# Cellphone.net
KiCad netlist of a schematic drawn in EAGLE
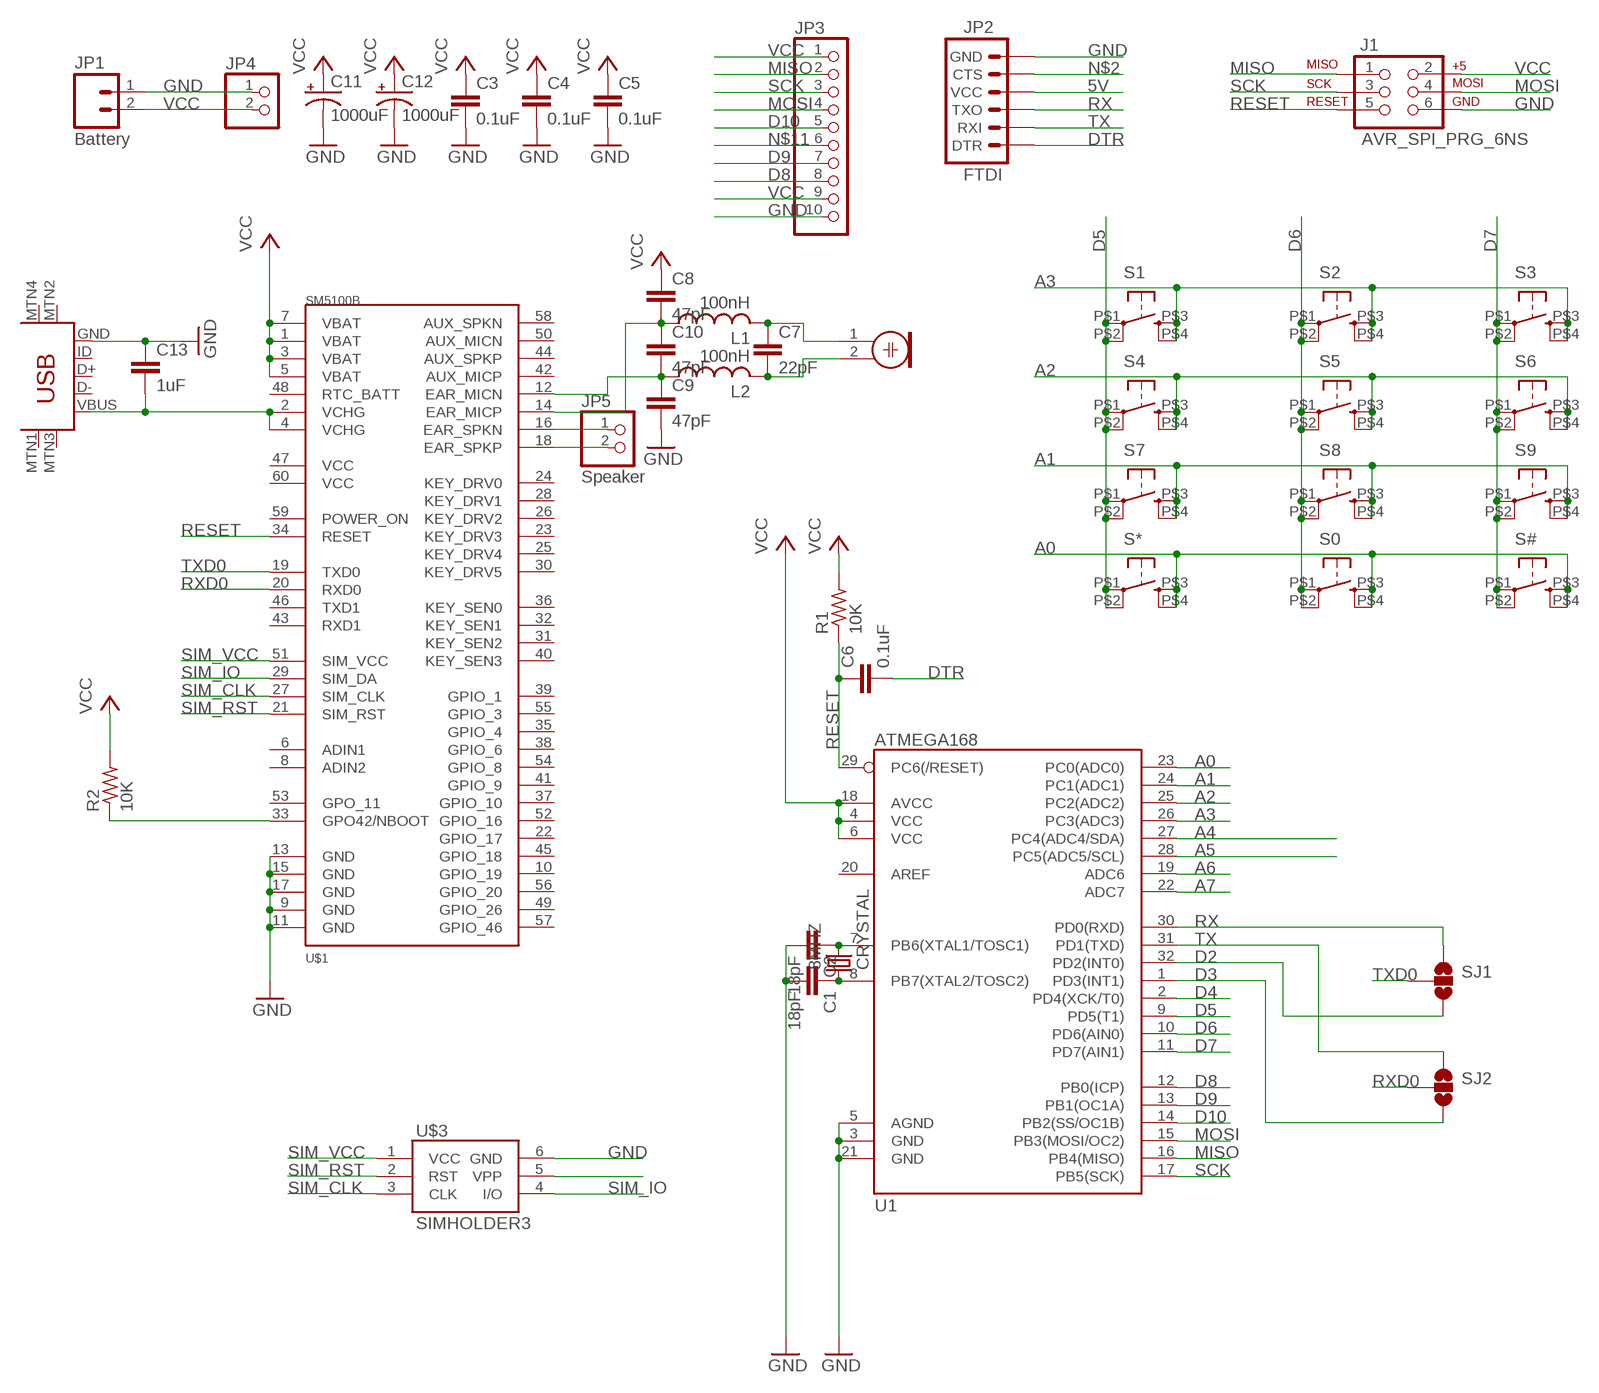
[diagram p0: schematic, sheet 1]

(export (version "E")
  (design (tool "Eeschema 10.0.6"))
  (components
    (comp (ref "8MHZ")
      (value "CRYSTAL")
      (footprint "eagle-import:2-SMD-5X3MM")
      (libsource (lib "eagle-import") (part "CRYSTAL"))
    )
    (comp (ref "C1")
      (value "18pF")
      (footprint "eagle-import:C1206")
      (libsource (lib "eagle-import") (part "C-EUC1206"))
    )
    (comp (ref "C2")
      (value "18pF")
      (footprint "eagle-import:C1206")
      (libsource (lib "eagle-import") (part "C-EUC1206"))
    )
    (comp (ref "C3")
      (value "0.1uF")
      (footprint "eagle-import:C1206")
      (libsource (lib "eagle-import") (part "C-EUC1206"))
    )
    (comp (ref "C4")
      (value "0.1uF")
      (footprint "eagle-import:C1206")
      (libsource (lib "eagle-import") (part "C-EUC1206"))
    )
    (comp (ref "C5")
      (value "0.1uF")
      (footprint "eagle-import:C1206")
      (libsource (lib "eagle-import") (part "C-EUC1206"))
    )
    (comp (ref "C6")
      (value "0.1uF")
      (footprint "eagle-import:C1206")
      (libsource (lib "eagle-import") (part "C-EUC1206"))
    )
    (comp (ref "C7")
      (value "22pF")
      (footprint "eagle-import:C1206")
      (libsource (lib "eagle-import") (part "C-EUC1206"))
    )
    (comp (ref "C8")
      (value "47pF")
      (footprint "eagle-import:C1206")
      (libsource (lib "eagle-import") (part "C-EUC1206"))
    )
    (comp (ref "C9")
      (value "47pF")
      (footprint "eagle-import:C1206")
      (libsource (lib "eagle-import") (part "C-EUC1206"))
    )
    (comp (ref "C10")
      (value "47pF")
      (footprint "eagle-import:C1206")
      (libsource (lib "eagle-import") (part "C-EUC1206"))
    )
    (comp (ref "C11")
      (value "1000uF")
      (footprint "eagle-import:D_7343-31R")
      (libsource (lib "eagle-import") (part "CPOL-USD/7343-31R"))
    )
    (comp (ref "C12")
      (value "1000uF")
      (footprint "eagle-import:D_7343-31R")
      (libsource (lib "eagle-import") (part "CPOL-USD/7343-31R"))
    )
    (comp (ref "C13")
      (value "1uF")
      (footprint "eagle-import:C1206")
      (libsource (lib "eagle-import") (part "C-EUC1206"))
    )
    (comp (ref "J1")
      (value "AVR_SPI_PRG_6NS")
      (footprint "eagle-import:2X3-NS")
      (libsource (lib "eagle-import") (part "AVR_SPI_PRG_6NS"))
    )
    (comp (ref "JP1")
      (value "Battery")
      (footprint "eagle-import:JST-2-SMD")
      (libsource (lib "eagle-import") (part "M02-JST-2MM-SMT"))
    )
    (comp (ref "JP2")
      (value "FTDI")
      (footprint "eagle-import:1X06")
      (libsource (lib "eagle-import") (part "ARDUINO_SERIAL_PROGRAMPTH"))
    )
    (comp (ref "JP3")
      (value "TFT160X128")
      (footprint "eagle-import:TFT1.8")
      (libsource (lib "eagle-import") (part "TFT160X128"))
    )
    (comp (ref "JP4")
      (value "PINHD-1X2")
      (footprint "eagle-import:1X02")
      (libsource (lib "eagle-import") (part "PINHD-1X2"))
    )
    (comp (ref "JP5")
      (value "Speaker")
      (footprint "eagle-import:1X02")
      (libsource (lib "eagle-import") (part "PINHD-1X2"))
    )
    (comp (ref "L1")
      (value "100nH")
      (footprint "eagle-import:L2012C")
      (libsource (lib "eagle-import") (part "L-USL2012C"))
    )
    (comp (ref "L2")
      (value "100nH")
      (footprint "eagle-import:L2012C")
      (libsource (lib "eagle-import") (part "L-USL2012C"))
    )
    (comp (ref "M1")
      (value "ELECTRET_MICROPHON-WM-64PC/64PK")
      (footprint "eagle-import:WM-64PC_64PK")
      (libsource (lib "eagle-import") (part "ELECTRET_MICROPHON-WM-64PC/64PK"))
    )
    (comp (ref "R1")
      (value "10K")
      (footprint "eagle-import:R1206")
      (libsource (lib "eagle-import") (part "R-US_R1206"))
    )
    (comp (ref "R2")
      (value "10K")
      (footprint "eagle-import:R1206")
      (libsource (lib "eagle-import") (part "R-US_R1206"))
    )
    (comp (ref "S#")
      (value "SWITCH-JLEAD")
      (footprint "eagle-import:BUTTON_6MM_JLEAD")
      (libsource (lib "eagle-import") (part "SWITCH-JLEAD"))
    )
    (comp (ref "S*")
      (value "SWITCH-JLEAD")
      (footprint "eagle-import:BUTTON_6MM_JLEAD")
      (libsource (lib "eagle-import") (part "SWITCH-JLEAD"))
    )
    (comp (ref "S0")
      (value "SWITCH-JLEAD")
      (footprint "eagle-import:BUTTON_6MM_JLEAD")
      (libsource (lib "eagle-import") (part "SWITCH-JLEAD"))
    )
    (comp (ref "S1")
      (value "SWITCH-JLEAD")
      (footprint "eagle-import:BUTTON_6MM_JLEAD")
      (libsource (lib "eagle-import") (part "SWITCH-JLEAD"))
    )
    (comp (ref "S2")
      (value "SWITCH-JLEAD")
      (footprint "eagle-import:BUTTON_6MM_JLEAD")
      (libsource (lib "eagle-import") (part "SWITCH-JLEAD"))
    )
    (comp (ref "S3")
      (value "SWITCH-JLEAD")
      (footprint "eagle-import:BUTTON_6MM_JLEAD")
      (libsource (lib "eagle-import") (part "SWITCH-JLEAD"))
    )
    (comp (ref "S4")
      (value "SWITCH-JLEAD")
      (footprint "eagle-import:BUTTON_6MM_JLEAD")
      (libsource (lib "eagle-import") (part "SWITCH-JLEAD"))
    )
    (comp (ref "S5")
      (value "SWITCH-JLEAD")
      (footprint "eagle-import:BUTTON_6MM_JLEAD")
      (libsource (lib "eagle-import") (part "SWITCH-JLEAD"))
    )
    (comp (ref "S6")
      (value "SWITCH-JLEAD")
      (footprint "eagle-import:BUTTON_6MM_JLEAD")
      (libsource (lib "eagle-import") (part "SWITCH-JLEAD"))
    )
    (comp (ref "S7")
      (value "SWITCH-JLEAD")
      (footprint "eagle-import:BUTTON_6MM_JLEAD")
      (libsource (lib "eagle-import") (part "SWITCH-JLEAD"))
    )
    (comp (ref "S8")
      (value "SWITCH-JLEAD")
      (footprint "eagle-import:BUTTON_6MM_JLEAD")
      (libsource (lib "eagle-import") (part "SWITCH-JLEAD"))
    )
    (comp (ref "S9")
      (value "SWITCH-JLEAD")
      (footprint "eagle-import:BUTTON_6MM_JLEAD")
      (libsource (lib "eagle-import") (part "SWITCH-JLEAD"))
    )
    (comp (ref "SJ1")
      (value "SOLDERJUMPER_2WAYPASTE1&2")
      (footprint "eagle-import:SJ_3_PASTE1&2")
      (libsource (lib "eagle-import") (part "SOLDERJUMPER_2WAYPASTE1&2"))
    )
    (comp (ref "SJ2")
      (value "SOLDERJUMPER_2WAYPASTE1&2")
      (footprint "eagle-import:SJ_3_PASTE1&2")
      (libsource (lib "eagle-import") (part "SOLDERJUMPER_2WAYPASTE1&2"))
    )
    (comp (ref "U$1")
      (value "SM5100B")
      (footprint "eagle-import:SM5100B")
      (libsource (lib "eagle-import") (part "SM5100B"))
    )
    (comp (ref "U$2")
      (value "USB-MINIB-5PIN")
      (footprint "eagle-import:USB-MINIB")
      (libsource (lib "eagle-import") (part "USB-MINIB-5PIN"))
    )
    (comp (ref "U$3")
      (value "SIMHOLDER3")
      (footprint "eagle-import:SIMHOLDER3")
      (libsource (lib "eagle-import") (part "SIMHOLDER3"))
    )
    (comp (ref "U1")
      (value "ATMEGA168")
      (footprint "eagle-import:TQFP32-08")
      (libsource (lib "eagle-import") (part "ATMEGA168"))
    )
  )
  (nets
    (net (code "1") (name "/5V") (class "Default")
      (node (ref "JP2") (pin "4") (pinfunction "VCC_4") (pintype "passive"))
    )
    (net (code "2") (name "/A0") (class "Default")
      (node (ref "S#") (pin "P$3") (pinfunction "S_P$3") (pintype "passive"))
      (node (ref "S#") (pin "P$4") (pinfunction "S1_P$4") (pintype "passive"))
      (node (ref "S*") (pin "P$3") (pinfunction "S_P$3") (pintype "passive"))
      (node (ref "S*") (pin "P$4") (pinfunction "S1_P$4") (pintype "passive"))
      (node (ref "S0") (pin "P$3") (pinfunction "S_P$3") (pintype "passive"))
      (node (ref "S0") (pin "P$4") (pinfunction "S1_P$4") (pintype "passive"))
      (node (ref "U1") (pin "23") (pinfunction "PC0(ADC0)_23") (pintype "bidirectional"))
    )
    (net (code "3") (name "/A1") (class "Default")
      (node (ref "S7") (pin "P$3") (pinfunction "S_P$3") (pintype "passive"))
      (node (ref "S7") (pin "P$4") (pinfunction "S1_P$4") (pintype "passive"))
      (node (ref "S8") (pin "P$3") (pinfunction "S_P$3") (pintype "passive"))
      (node (ref "S8") (pin "P$4") (pinfunction "S1_P$4") (pintype "passive"))
      (node (ref "S9") (pin "P$3") (pinfunction "S_P$3") (pintype "passive"))
      (node (ref "S9") (pin "P$4") (pinfunction "S1_P$4") (pintype "passive"))
      (node (ref "U1") (pin "24") (pinfunction "PC1(ADC1)_24") (pintype "bidirectional"))
    )
    (net (code "4") (name "/A2") (class "Default")
      (node (ref "S4") (pin "P$3") (pinfunction "S_P$3") (pintype "passive"))
      (node (ref "S4") (pin "P$4") (pinfunction "S1_P$4") (pintype "passive"))
      (node (ref "S5") (pin "P$3") (pinfunction "S_P$3") (pintype "passive"))
      (node (ref "S5") (pin "P$4") (pinfunction "S1_P$4") (pintype "passive"))
      (node (ref "S6") (pin "P$3") (pinfunction "S_P$3") (pintype "passive"))
      (node (ref "S6") (pin "P$4") (pinfunction "S1_P$4") (pintype "passive"))
      (node (ref "U1") (pin "25") (pinfunction "PC2(ADC2)_25") (pintype "bidirectional"))
    )
    (net (code "5") (name "/A3") (class "Default")
      (node (ref "S1") (pin "P$3") (pinfunction "S_P$3") (pintype "passive"))
      (node (ref "S1") (pin "P$4") (pinfunction "S1_P$4") (pintype "passive"))
      (node (ref "S2") (pin "P$3") (pinfunction "S_P$3") (pintype "passive"))
      (node (ref "S2") (pin "P$4") (pinfunction "S1_P$4") (pintype "passive"))
      (node (ref "S3") (pin "P$3") (pinfunction "S_P$3") (pintype "passive"))
      (node (ref "S3") (pin "P$4") (pinfunction "S1_P$4") (pintype "passive"))
      (node (ref "U1") (pin "26") (pinfunction "PC3(ADC3)_26") (pintype "bidirectional"))
    )
    (net (code "6") (name "/A4") (class "Default")
      (node (ref "U1") (pin "27") (pinfunction "PC4(ADC4/SDA)_27") (pintype "bidirectional"))
    )
    (net (code "7") (name "/A5") (class "Default")
      (node (ref "U1") (pin "28") (pinfunction "PC5(ADC5/SCL)_28") (pintype "bidirectional"))
    )
    (net (code "8") (name "/A6") (class "Default")
      (node (ref "U1") (pin "19") (pinfunction "ADC6_19") (pintype "bidirectional"))
    )
    (net (code "9") (name "/A7") (class "Default")
      (node (ref "U1") (pin "22") (pinfunction "ADC7_22") (pintype "bidirectional"))
    )
    (net (code "10") (name "/D2") (class "Default")
      (node (ref "SJ1") (pin "3") (pinfunction "3_3") (pintype "passive"))
      (node (ref "U1") (pin "32") (pinfunction "PD2(INT0)_32") (pintype "bidirectional"))
    )
    (net (code "11") (name "/D3") (class "Default")
      (node (ref "SJ2") (pin "3") (pinfunction "3_3") (pintype "passive"))
      (node (ref "U1") (pin "1") (pinfunction "PD3(INT1)_1") (pintype "bidirectional"))
    )
    (net (code "12") (name "/D4") (class "Default")
      (node (ref "U1") (pin "2") (pinfunction "PD4(XCK/T0)_2") (pintype "bidirectional"))
    )
    (net (code "13") (name "/D5") (class "Default")
      (node (ref "S*") (pin "P$1") (pinfunction "P_P$1") (pintype "passive"))
      (node (ref "S*") (pin "P$2") (pinfunction "P1_P$2") (pintype "passive"))
      (node (ref "S1") (pin "P$1") (pinfunction "P_P$1") (pintype "passive"))
      (node (ref "S1") (pin "P$2") (pinfunction "P1_P$2") (pintype "passive"))
      (node (ref "S4") (pin "P$1") (pinfunction "P_P$1") (pintype "passive"))
      (node (ref "S4") (pin "P$2") (pinfunction "P1_P$2") (pintype "passive"))
      (node (ref "S7") (pin "P$1") (pinfunction "P_P$1") (pintype "passive"))
      (node (ref "S7") (pin "P$2") (pinfunction "P1_P$2") (pintype "passive"))
      (node (ref "U1") (pin "9") (pinfunction "PD5(T1)_9") (pintype "bidirectional"))
    )
    (net (code "14") (name "/D6") (class "Default")
      (node (ref "S0") (pin "P$1") (pinfunction "P_P$1") (pintype "passive"))
      (node (ref "S0") (pin "P$2") (pinfunction "P1_P$2") (pintype "passive"))
      (node (ref "S2") (pin "P$1") (pinfunction "P_P$1") (pintype "passive"))
      (node (ref "S2") (pin "P$2") (pinfunction "P1_P$2") (pintype "passive"))
      (node (ref "S5") (pin "P$1") (pinfunction "P_P$1") (pintype "passive"))
      (node (ref "S5") (pin "P$2") (pinfunction "P1_P$2") (pintype "passive"))
      (node (ref "S8") (pin "P$1") (pinfunction "P_P$1") (pintype "passive"))
      (node (ref "S8") (pin "P$2") (pinfunction "P1_P$2") (pintype "passive"))
      (node (ref "U1") (pin "10") (pinfunction "PD6(AIN0)_10") (pintype "bidirectional"))
    )
    (net (code "15") (name "/D7") (class "Default")
      (node (ref "S#") (pin "P$1") (pinfunction "P_P$1") (pintype "passive"))
      (node (ref "S#") (pin "P$2") (pinfunction "P1_P$2") (pintype "passive"))
      (node (ref "S3") (pin "P$1") (pinfunction "P_P$1") (pintype "passive"))
      (node (ref "S3") (pin "P$2") (pinfunction "P1_P$2") (pintype "passive"))
      (node (ref "S6") (pin "P$1") (pinfunction "P_P$1") (pintype "passive"))
      (node (ref "S6") (pin "P$2") (pinfunction "P1_P$2") (pintype "passive"))
      (node (ref "S9") (pin "P$1") (pinfunction "P_P$1") (pintype "passive"))
      (node (ref "S9") (pin "P$2") (pinfunction "P1_P$2") (pintype "passive"))
      (node (ref "U1") (pin "11") (pinfunction "PD7(AIN1)_11") (pintype "bidirectional"))
    )
    (net (code "16") (name "/D8") (class "Default")
      (node (ref "JP3") (pin "8") (pinfunction "RESET_8") (pintype "passive"))
      (node (ref "U1") (pin "12") (pinfunction "PB0(ICP)_12") (pintype "bidirectional"))
    )
    (net (code "17") (name "/D9") (class "Default")
      (node (ref "JP3") (pin "7") (pinfunction "D/C_7") (pintype "passive"))
      (node (ref "U1") (pin "13") (pinfunction "PB1(OC1A)_13") (pintype "bidirectional"))
    )
    (net (code "18") (name "/D10") (class "Default")
      (node (ref "JP3") (pin "5") (pinfunction "TFT_CS_5") (pintype "passive"))
      (node (ref "U1") (pin "14") (pinfunction "PB2(SS/OC1B)_14") (pintype "bidirectional"))
    )
    (net (code "19") (name "/DTR") (class "Default")
      (node (ref "C6") (pin "2") (pinfunction "2_2") (pintype "passive"))
      (node (ref "JP2") (pin "1") (pinfunction "DTR_1") (pintype "passive"))
    )
    (net (code "20") (name "/MISO") (class "Default")
      (node (ref "J1") (pin "1") (pinfunction "1_1") (pintype "passive"))
      (node (ref "JP3") (pin "2") (pinfunction "MISO_2") (pintype "passive"))
      (node (ref "U1") (pin "16") (pinfunction "PB4(MISO)_16") (pintype "bidirectional"))
    )
    (net (code "21") (name "/MOSI") (class "Default")
      (node (ref "J1") (pin "4") (pinfunction "4_4") (pintype "passive"))
      (node (ref "JP3") (pin "4") (pinfunction "MOSI_4") (pintype "passive"))
      (node (ref "U1") (pin "15") (pinfunction "PB3(MOSI/OC2)_15") (pintype "bidirectional"))
    )
    (net (code "22") (name "/N$2") (class "Default")
      (node (ref "JP2") (pin "5") (pinfunction "CTS_5") (pintype "passive"))
    )
    (net (code "23") (name "/N$11") (class "Default")
      (node (ref "JP3") (pin "6") (pinfunction "CARD_CS_6") (pintype "passive"))
    )
    (net (code "24") (name "/RESET") (class "Default")
      (node (ref "C6") (pin "1") (pinfunction "1_1") (pintype "passive"))
      (node (ref "J1") (pin "5") (pinfunction "5_5") (pintype "passive"))
      (node (ref "R1") (pin "1") (pinfunction "1_1") (pintype "passive"))
      (node (ref "U$1") (pin "34") (pinfunction "RESET_34") (pintype "bidirectional"))
      (node (ref "U1") (pin "29") (pinfunction "PC6(/RESET)_29") (pintype "bidirectional"))
    )
    (net (code "25") (name "/RX") (class "Default")
      (node (ref "JP2") (pin "3") (pinfunction "TXO_3") (pintype "passive"))
      (node (ref "SJ1") (pin "1") (pinfunction "1_1") (pintype "passive"))
      (node (ref "U1") (pin "30") (pinfunction "PD0(RXD)_30") (pintype "bidirectional"))
    )
    (net (code "26") (name "/RXD0") (class "Default")
      (node (ref "SJ2") (pin "2") (pinfunction "2_2") (pintype "passive"))
      (node (ref "U$1") (pin "20") (pinfunction "RXD0_20") (pintype "bidirectional"))
    )
    (net (code "27") (name "/SCK") (class "Default")
      (node (ref "J1") (pin "3") (pinfunction "3_3") (pintype "passive"))
      (node (ref "JP3") (pin "3") (pinfunction "SCK_3") (pintype "passive"))
      (node (ref "U1") (pin "17") (pinfunction "PB5(SCK)_17") (pintype "bidirectional"))
    )
    (net (code "28") (name "/SIM_CLK") (class "Default")
      (node (ref "U$1") (pin "27") (pinfunction "SIM_CLK_27") (pintype "bidirectional"))
      (node (ref "U$3") (pin "3") (pinfunction "CLK_3") (pintype "bidirectional"))
    )
    (net (code "29") (name "/SIM_IO") (class "Default")
      (node (ref "U$1") (pin "29") (pinfunction "SIM_DA_29") (pintype "bidirectional"))
      (node (ref "U$3") (pin "4") (pinfunction "I/O_4") (pintype "bidirectional"))
    )
    (net (code "30") (name "/SIM_RST") (class "Default")
      (node (ref "U$1") (pin "21") (pinfunction "SIM_RST_21") (pintype "bidirectional"))
      (node (ref "U$3") (pin "2") (pinfunction "RST_2") (pintype "bidirectional"))
    )
    (net (code "31") (name "/SIM_VCC") (class "Default")
      (node (ref "U$1") (pin "51") (pinfunction "SIM_VCC_51") (pintype "bidirectional"))
      (node (ref "U$3") (pin "1") (pinfunction "VCC_1") (pintype "bidirectional"))
    )
    (net (code "32") (name "/TX") (class "Default")
      (node (ref "JP2") (pin "2") (pinfunction "RXI_2") (pintype "passive"))
      (node (ref "SJ2") (pin "1") (pinfunction "1_1") (pintype "passive"))
      (node (ref "U1") (pin "31") (pinfunction "PD1(TXD)_31") (pintype "bidirectional"))
    )
    (net (code "33") (name "/TXD0") (class "Default")
      (node (ref "SJ1") (pin "2") (pinfunction "2_2") (pintype "passive"))
      (node (ref "U$1") (pin "19") (pinfunction "TXD0_19") (pintype "bidirectional"))
    )
    (net (code "34") (name "GND") (class "Default")
      (node (ref "C1") (pin "2") (pinfunction "2_2") (pintype "passive"))
      (node (ref "C11") (pin "-") (pinfunction "-_-") (pintype "passive"))
      (node (ref "C12") (pin "-") (pinfunction "-_-") (pintype "passive"))
      (node (ref "C13") (pin "1") (pinfunction "1_1") (pintype "passive"))
      (node (ref "C2") (pin "2") (pinfunction "2_2") (pintype "passive"))
      (node (ref "C3") (pin "2") (pinfunction "2_2") (pintype "passive"))
      (node (ref "C4") (pin "2") (pinfunction "2_2") (pintype "passive"))
      (node (ref "C5") (pin "2") (pinfunction "2_2") (pintype "passive"))
      (node (ref "C9") (pin "2") (pinfunction "2_2") (pintype "passive"))
      (node (ref "J1") (pin "6") (pinfunction "6_6") (pintype "passive"))
      (node (ref "JP1") (pin "1") (pinfunction "2_1") (pintype "passive"))
      (node (ref "JP2") (pin "6") (pinfunction "GND_6") (pintype "passive"))
      (node (ref "JP3") (pin "10") (pinfunction "GND_10") (pintype "passive"))
      (node (ref "JP4") (pin "1") (pinfunction "1_1") (pintype "passive"))
      (node (ref "U$1") (pin "11") (pinfunction "GND_11") (pintype "bidirectional"))
      (node (ref "U$1") (pin "13") (pinfunction "GND_13") (pintype "bidirectional"))
      (node (ref "U$1") (pin "15") (pinfunction "GND_15") (pintype "bidirectional"))
      (node (ref "U$1") (pin "17") (pinfunction "GND_17") (pintype "bidirectional"))
      (node (ref "U$1") (pin "9") (pinfunction "GND_9") (pintype "bidirectional"))
      (node (ref "U$2") (pin "GND") (pinfunction "GND_GND") (pintype "bidirectional"))
      (node (ref "U$3") (pin "6") (pinfunction "GND_6") (pintype "bidirectional"))
      (node (ref "U1") (pin "21") (pinfunction "GND_21") (pintype "bidirectional"))
      (node (ref "U1") (pin "3") (pinfunction "GND_3") (pintype "bidirectional"))
      (node (ref "U1") (pin "5") (pinfunction "AGND_5") (pintype "bidirectional"))
    )
    (net (code "35") (name "Net-(8MHZ-1)") (class "Default")
      (node (ref "8MHZ") (pin "P$1") (pinfunction "1_P$1") (pintype "passive"))
      (node (ref "C1") (pin "1") (pinfunction "1_1") (pintype "passive"))
      (node (ref "U1") (pin "8") (pinfunction "PB7(XTAL2/TOSC2)_8") (pintype "bidirectional"))
    )
    (net (code "36") (name "Net-(8MHZ-2)") (class "Default")
      (node (ref "8MHZ") (pin "P$2") (pinfunction "2_P$2") (pintype "passive"))
      (node (ref "C2") (pin "1") (pinfunction "1_1") (pintype "passive"))
      (node (ref "U1") (pin "7") (pinfunction "PB6(XTAL1/TOSC1)_7") (pintype "bidirectional"))
    )
    (net (code "37") (name "Net-(C7-Pad1)") (class "Default")
      (node (ref "C7") (pin "1") (pinfunction "1_1") (pintype "passive"))
      (node (ref "L1") (pin "2") (pinfunction "2_2") (pintype "passive"))
      (node (ref "M1") (pin "1") (pinfunction "1_1") (pintype "passive"))
    )
    (net (code "38") (name "Net-(C7-Pad2)") (class "Default")
      (node (ref "C7") (pin "2") (pinfunction "2_2") (pintype "passive"))
      (node (ref "L2") (pin "2") (pinfunction "2_2") (pintype "passive"))
      (node (ref "M1") (pin "2") (pinfunction "2_2") (pintype "passive"))
    )
    (net (code "39") (name "Net-(C13-Pad2)") (class "Default")
      (node (ref "C13") (pin "2") (pinfunction "2_2") (pintype "passive"))
      (node (ref "U$1") (pin "2") (pinfunction "VCHG_2") (pintype "bidirectional"))
      (node (ref "U$1") (pin "4") (pinfunction "VCHG_4") (pintype "bidirectional"))
      (node (ref "U$2") (pin "VBUS") (pinfunction "VBUS_VBUS") (pintype "bidirectional"))
    )
    (net (code "40") (name "Net-(U$1-EAR_MICN)") (class "Default")
      (node (ref "C10") (pin "2") (pinfunction "2_2") (pintype "passive"))
      (node (ref "C9") (pin "1") (pinfunction "1_1") (pintype "passive"))
      (node (ref "L2") (pin "1") (pinfunction "1_1") (pintype "passive"))
      (node (ref "U$1") (pin "12") (pinfunction "EAR_MICN_12") (pintype "bidirectional"))
    )
    (net (code "41") (name "Net-(U$1-EAR_MICP)") (class "Default")
      (node (ref "C10") (pin "1") (pinfunction "1_1") (pintype "passive"))
      (node (ref "C8") (pin "2") (pinfunction "2_2") (pintype "passive"))
      (node (ref "L1") (pin "1") (pinfunction "1_1") (pintype "passive"))
      (node (ref "U$1") (pin "14") (pinfunction "EAR_MICP_14") (pintype "bidirectional"))
    )
    (net (code "42") (name "Net-(U$1-EAR_SPKN)") (class "Default")
      (node (ref "JP5") (pin "1") (pinfunction "1_1") (pintype "passive"))
      (node (ref "U$1") (pin "16") (pinfunction "EAR_SPKN_16") (pintype "bidirectional"))
    )
    (net (code "43") (name "Net-(U$1-EAR_SPKP)") (class "Default")
      (node (ref "JP5") (pin "2") (pinfunction "2_2") (pintype "passive"))
      (node (ref "U$1") (pin "18") (pinfunction "EAR_SPKP_18") (pintype "bidirectional"))
    )
    (net (code "44") (name "Net-(U$1-GPO42{slash}NBOOT)") (class "Default")
      (node (ref "R2") (pin "1") (pinfunction "1_1") (pintype "passive"))
      (node (ref "U$1") (pin "33") (pinfunction "GPO42/NBOOT_33") (pintype "bidirectional"))
    )
    (net (code "45") (name "VCC") (class "Default")
      (node (ref "C11") (pin "+") (pinfunction "+_+") (pintype "passive"))
      (node (ref "C12") (pin "+") (pinfunction "+_+") (pintype "passive"))
      (node (ref "C3") (pin "1") (pinfunction "1_1") (pintype "passive"))
      (node (ref "C4") (pin "1") (pinfunction "1_1") (pintype "passive"))
      (node (ref "C5") (pin "1") (pinfunction "1_1") (pintype "passive"))
      (node (ref "C8") (pin "1") (pinfunction "1_1") (pintype "passive"))
      (node (ref "J1") (pin "2") (pinfunction "2_2") (pintype "passive"))
      (node (ref "JP1") (pin "2") (pinfunction "1_2") (pintype "passive"))
      (node (ref "JP3") (pin "1") (pinfunction "LITE_1") (pintype "passive"))
      (node (ref "JP3") (pin "9") (pinfunction "VCC_9") (pintype "passive"))
      (node (ref "JP4") (pin "2") (pinfunction "2_2") (pintype "passive"))
      (node (ref "R1") (pin "2") (pinfunction "2_2") (pintype "passive"))
      (node (ref "R2") (pin "2") (pinfunction "2_2") (pintype "passive"))
      (node (ref "U$1") (pin "1") (pinfunction "VBAT_1") (pintype "bidirectional"))
      (node (ref "U$1") (pin "3") (pinfunction "VBAT_3") (pintype "bidirectional"))
      (node (ref "U$1") (pin "5") (pinfunction "VBAT_5") (pintype "bidirectional"))
      (node (ref "U$1") (pin "7") (pinfunction "VBAT_7") (pintype "bidirectional"))
      (node (ref "U1") (pin "18") (pinfunction "AVCC_18") (pintype "bidirectional"))
      (node (ref "U1") (pin "4") (pinfunction "VCC_4") (pintype "bidirectional"))
      (node (ref "U1") (pin "6") (pinfunction "VCC_6") (pintype "bidirectional"))
    )
    (net (code "46") (name "unconnected-(U$1-ADIN1-Pad6)") (class "Default")
      (node (ref "U$1") (pin "6") (pinfunction "ADIN1_6") (pintype "bidirectional"))
    )
    (net (code "47") (name "unconnected-(U$1-ADIN2-Pad8)") (class "Default")
      (node (ref "U$1") (pin "8") (pinfunction "ADIN2_8") (pintype "bidirectional"))
    )
    (net (code "48") (name "unconnected-(U$1-AUX_MICN-Pad50)") (class "Default")
      (node (ref "U$1") (pin "50") (pinfunction "AUX_MICN_50") (pintype "bidirectional"))
    )
    (net (code "49") (name "unconnected-(U$1-AUX_MICP-Pad42)") (class "Default")
      (node (ref "U$1") (pin "42") (pinfunction "AUX_MICP_42") (pintype "bidirectional"))
    )
    (net (code "50") (name "unconnected-(U$1-AUX_SPKN-Pad58)") (class "Default")
      (node (ref "U$1") (pin "58") (pinfunction "AUX_SPKN_58") (pintype "bidirectional"))
    )
    (net (code "51") (name "unconnected-(U$1-AUX_SPKP-Pad44)") (class "Default")
      (node (ref "U$1") (pin "44") (pinfunction "AUX_SPKP_44") (pintype "bidirectional"))
    )
    (net (code "52") (name "unconnected-(U$1-GPIO_1-Pad39)") (class "Default")
      (node (ref "U$1") (pin "39") (pinfunction "GPIO_1_39") (pintype "bidirectional"))
    )
    (net (code "53") (name "unconnected-(U$1-GPIO_3-Pad55)") (class "Default")
      (node (ref "U$1") (pin "55") (pinfunction "GPIO_3_55") (pintype "bidirectional"))
    )
    (net (code "54") (name "unconnected-(U$1-GPIO_4-Pad35)") (class "Default")
      (node (ref "U$1") (pin "35") (pinfunction "GPIO_4_35") (pintype "bidirectional"))
    )
    (net (code "55") (name "unconnected-(U$1-GPIO_6-Pad38)") (class "Default")
      (node (ref "U$1") (pin "38") (pinfunction "GPIO_6_38") (pintype "bidirectional"))
    )
    (net (code "56") (name "unconnected-(U$1-GPIO_8-Pad54)") (class "Default")
      (node (ref "U$1") (pin "54") (pinfunction "GPIO_8_54") (pintype "bidirectional"))
    )
    (net (code "57") (name "unconnected-(U$1-GPIO_9-Pad41)") (class "Default")
      (node (ref "U$1") (pin "41") (pinfunction "GPIO_9_41") (pintype "bidirectional"))
    )
    (net (code "58") (name "unconnected-(U$1-GPIO_10-Pad37)") (class "Default")
      (node (ref "U$1") (pin "37") (pinfunction "GPIO_10_37") (pintype "bidirectional"))
    )
    (net (code "59") (name "unconnected-(U$1-GPIO_16-Pad52)") (class "Default")
      (node (ref "U$1") (pin "52") (pinfunction "GPIO_16_52") (pintype "bidirectional"))
    )
    (net (code "60") (name "unconnected-(U$1-GPIO_17-Pad22)") (class "Default")
      (node (ref "U$1") (pin "22") (pinfunction "GPIO_17_22") (pintype "bidirectional"))
    )
    (net (code "61") (name "unconnected-(U$1-GPIO_18-Pad45)") (class "Default")
      (node (ref "U$1") (pin "45") (pinfunction "GPIO_18_45") (pintype "bidirectional"))
    )
    (net (code "62") (name "unconnected-(U$1-GPIO_19-Pad10)") (class "Default")
      (node (ref "U$1") (pin "10") (pinfunction "GPIO_19_10") (pintype "bidirectional"))
    )
    (net (code "63") (name "unconnected-(U$1-GPIO_20-Pad56)") (class "Default")
      (node (ref "U$1") (pin "56") (pinfunction "GPIO_20_56") (pintype "bidirectional"))
    )
    (net (code "64") (name "unconnected-(U$1-GPIO_26-Pad49)") (class "Default")
      (node (ref "U$1") (pin "49") (pinfunction "GPIO_26_49") (pintype "bidirectional"))
    )
    (net (code "65") (name "unconnected-(U$1-GPIO_46-Pad57)") (class "Default")
      (node (ref "U$1") (pin "57") (pinfunction "GPIO_46_57") (pintype "bidirectional"))
    )
    (net (code "66") (name "unconnected-(U$1-GPO_11-Pad53)") (class "Default")
      (node (ref "U$1") (pin "53") (pinfunction "GPO_11_53") (pintype "bidirectional"))
    )
    (net (code "67") (name "unconnected-(U$1-KEY_DRV0-Pad24)") (class "Default")
      (node (ref "U$1") (pin "24") (pinfunction "KEY_DRV0_24") (pintype "bidirectional"))
    )
    (net (code "68") (name "unconnected-(U$1-KEY_DRV1-Pad28)") (class "Default")
      (node (ref "U$1") (pin "28") (pinfunction "KEY_DRV1_28") (pintype "bidirectional"))
    )
    (net (code "69") (name "unconnected-(U$1-KEY_DRV2-Pad26)") (class "Default")
      (node (ref "U$1") (pin "26") (pinfunction "KEY_DRV2_26") (pintype "bidirectional"))
    )
    (net (code "70") (name "unconnected-(U$1-KEY_DRV3-Pad23)") (class "Default")
      (node (ref "U$1") (pin "23") (pinfunction "KEY_DRV3_23") (pintype "bidirectional"))
    )
    (net (code "71") (name "unconnected-(U$1-KEY_DRV4-Pad25)") (class "Default")
      (node (ref "U$1") (pin "25") (pinfunction "KEY_DRV4_25") (pintype "bidirectional"))
    )
    (net (code "72") (name "unconnected-(U$1-KEY_DRV5-Pad30)") (class "Default")
      (node (ref "U$1") (pin "30") (pinfunction "KEY_DRV5_30") (pintype "bidirectional"))
    )
    (net (code "73") (name "unconnected-(U$1-KEY_SEN0-Pad36)") (class "Default")
      (node (ref "U$1") (pin "36") (pinfunction "KEY_SEN0_36") (pintype "bidirectional"))
    )
    (net (code "74") (name "unconnected-(U$1-KEY_SEN1-Pad32)") (class "Default")
      (node (ref "U$1") (pin "32") (pinfunction "KEY_SEN1_32") (pintype "bidirectional"))
    )
    (net (code "75") (name "unconnected-(U$1-KEY_SEN2-Pad31)") (class "Default")
      (node (ref "U$1") (pin "31") (pinfunction "KEY_SEN2_31") (pintype "bidirectional"))
    )
    (net (code "76") (name "unconnected-(U$1-KEY_SEN3-Pad40)") (class "Default")
      (node (ref "U$1") (pin "40") (pinfunction "KEY_SEN3_40") (pintype "bidirectional"))
    )
    (net (code "77") (name "unconnected-(U$1-POWER_ON-Pad59)") (class "Default")
      (node (ref "U$1") (pin "59") (pinfunction "POWER_ON_59") (pintype "bidirectional"))
    )
    (net (code "78") (name "unconnected-(U$1-RTC_BATT-Pad48)") (class "Default")
      (node (ref "U$1") (pin "48") (pinfunction "RTC_BATT_48") (pintype "bidirectional"))
    )
    (net (code "79") (name "unconnected-(U$1-RXD1-Pad43)") (class "Default")
      (node (ref "U$1") (pin "43") (pinfunction "RXD1_43") (pintype "bidirectional"))
    )
    (net (code "80") (name "unconnected-(U$1-TXD1-Pad46)") (class "Default")
      (node (ref "U$1") (pin "46") (pinfunction "TXD1_46") (pintype "bidirectional"))
    )
    (net (code "81") (name "unconnected-(U$1-VCC-Pad47)") (class "Default")
      (node (ref "U$1") (pin "47") (pinfunction "VCC_47") (pintype "bidirectional"))
    )
    (net (code "82") (name "unconnected-(U$1-VCC-Pad60)") (class "Default")
      (node (ref "U$1") (pin "60") (pinfunction "VCC_60") (pintype "bidirectional"))
    )
    (net (code "83") (name "unconnected-(U$2-MTN1-PadMTN3)") (class "Default")
      (node (ref "U$2") (pin "MTN3") (pinfunction "MTN1_MTN3") (pintype "bidirectional"))
    )
    (net (code "84") (name "unconnected-(U$2-MTN2-PadMTN1)") (class "Default")
      (node (ref "U$2") (pin "MTN1") (pinfunction "MTN2_MTN1") (pintype "bidirectional"))
    )
    (net (code "85") (name "unconnected-(U$2-MTN3-PadMTN2)") (class "Default")
      (node (ref "U$2") (pin "MTN2") (pinfunction "MTN3_MTN2") (pintype "bidirectional"))
    )
    (net (code "86") (name "unconnected-(U$2-PadD+)") (class "Default")
      (node (ref "U$2") (pin "D+") (pinfunction "D+_D+") (pintype "bidirectional"))
    )
    (net (code "87") (name "unconnected-(U$2-PadD-)") (class "Default")
      (node (ref "U$2") (pin "D-") (pinfunction "D-_D-") (pintype "bidirectional"))
    )
    (net (code "88") (name "unconnected-(U$2-PadID)") (class "Default")
      (node (ref "U$2") (pin "ID") (pinfunction "ID_ID") (pintype "bidirectional"))
    )
    (net (code "89") (name "unconnected-(U$2-PadMTN4)") (class "Default")
      (node (ref "U$2") (pin "MTN4") (pinfunction "MTN4_MTN4") (pintype "bidirectional"))
    )
    (net (code "90") (name "unconnected-(U$3-VPP-Pad5)") (class "Default")
      (node (ref "U$3") (pin "5") (pinfunction "VPP_5") (pintype "bidirectional"))
    )
    (net (code "91") (name "unconnected-(U1-AREF-Pad20)") (class "Default")
      (node (ref "U1") (pin "20") (pinfunction "AREF_20") (pintype "bidirectional"))
    )
  )
)
